# 11_-POWER_BACKUP.net
KiCad netlist of a schematic drawn in Altium Designer
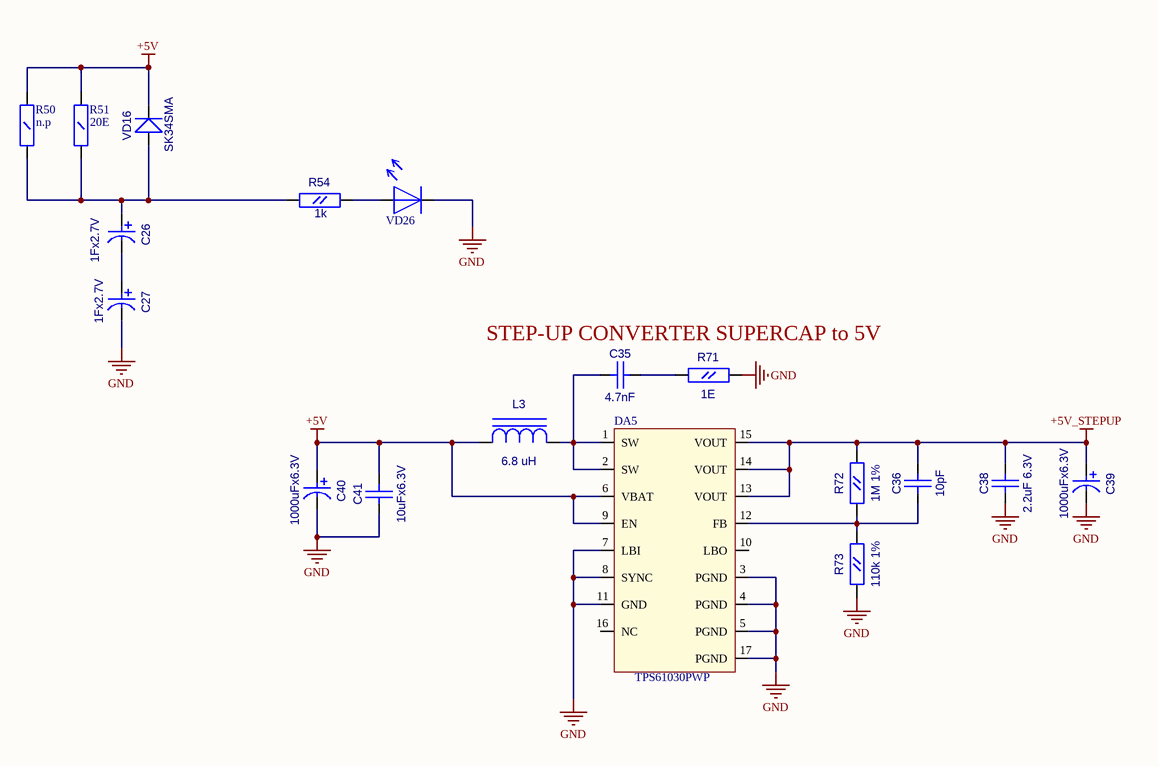
[diagram p0: [11]-POWER_BACKUP.SchDoc]

(export (version "E")
  (design (tool "Eeschema 10.0.6"))
  (components
    (comp (ref "C26")
      (value "1Fx2.7V")
      (footprint "CC8X11.5_L")
      (description "Radial capacitor")
      (libsource (lib "fizik_lib") (part "CAP_8mm"))
    )
    (comp (ref "C27")
      (value "1Fx2.7V")
      (footprint "CC8X11.5_L")
      (description "Radial capacitor")
      (libsource (lib "fizik_lib") (part "CAP_8mm"))
    )
    (comp (ref "C35")
      (value "4.7nF")
      (footprint "CC0603")
      (description "CC0603")
      (libsource (lib "gprs_modem_2") (part "CC0603"))
    )
    (comp (ref "C36")
      (value "10pF")
      (footprint "CC0603")
      (description "CC0603")
      (libsource (lib "gprs_modem_2") (part "CC0603"))
    )
    (comp (ref "C38")
      (value "2.2uF 6.3V")
      (footprint "CC0805")
      (description "CC0805")
      (libsource (lib "gprs_modem_2") (part "CC0805"))
    )
    (comp (ref "C39")
      (value "1000uFx6.3V")
      (footprint "CC8X3.5")
      (description "CAP0.35")
      (libsource (lib "gprs_modem_2") (part "CAP0.35"))
    )
    (comp (ref "C40")
      (value "1000uFx6.3V")
      (footprint "CC8X3.5")
      (description "CAP0.35")
      (libsource (lib "gprs_modem_2") (part "CAP0.35"))
    )
    (comp (ref "C41")
      (value "10uFx6.3V")
      (footprint "CC0805")
      (description "CC0805")
      (libsource (lib "gprs_modem_2") (part "CC0805"))
    )
    (comp (ref "DA5")
      (value "TPS61030PWP")
      (footprint "R-PDSO-G16")
      (description "Boost converter")
      (libsource (lib "gprs_modem") (part "TPS61030PWP"))
    )
    (comp (ref "L3")
      (value "6.8 uH")
      (footprint "SDR0805")
      (description "SDR0805")
      (libsource (lib "gprs_modem_2") (part "SDR0805"))
    )
    (comp (ref "R50")
      (value "n.p")
      (footprint "R2512")
      (description "Resistor 2512 1W")
      (libsource (lib "fizik_lib") (part "RC2512"))
    )
    (comp (ref "R51")
      (value "20E")
      (footprint "R2512")
      (description "Resistor 2512 1W")
      (libsource (lib "fizik_lib") (part "RC2512"))
    )
    (comp (ref "R54")
      (value "1k")
      (footprint "RC0603")
      (description "RC0603")
      (libsource (lib "fizik_lib") (part "RC0603"))
    )
    (comp (ref "R71")
      (value "1E")
      (footprint "RC0603")
      (description "RC0603")
      (libsource (lib "gprs_modem_2") (part "RC0603"))
    )
    (comp (ref "R72")
      (value "1M 1%")
      (footprint "RC0603")
      (description "RC0603")
      (libsource (lib "gprs_modem_2") (part "RC0603"))
    )
    (comp (ref "R73")
      (value "110k 1%")
      (footprint "RC0603")
      (description "RC0603")
      (libsource (lib "gprs_modem_2") (part "RC0603"))
    )
    (comp (ref "VD16")
      (value "SK34SMA")
      (footprint "SMA")
      (description "Schottky Rectifier")
      (libsource (lib "gprs_modem") (part "SK34SMA"))
    )
    (comp (ref "VD26")
      (value "LED_0805")
      (footprint "LED0805")
      (libsource (lib "fizik_lib") (part "LED_0805"))
    )
  )
  (nets
    (net (code "1") (name "+5V") (class "Default")
      (node (ref "C40") (pin "1") (pintype "passive"))
      (node (ref "C41") (pin "2") (pinfunction "B_2") (pintype "passive"))
      (node (ref "DA5") (pin "6") (pinfunction "VBAT_6") (pintype "passive"))
      (node (ref "DA5") (pin "9") (pinfunction "EN_9") (pintype "passive"))
      (node (ref "L3") (pin "1") (pinfunction "C_1") (pintype "passive"))
      (node (ref "R50") (pin "2") (pinfunction "B_2") (pintype "passive"))
      (node (ref "R51") (pin "2") (pinfunction "B_2") (pintype "passive"))
      (node (ref "VD16") (pin "2") (pinfunction "K_2") (pintype "passive"))
    )
    (net (code "2") (name "+5V_STEPUP") (class "Default")
      (node (ref "C36") (pin "2") (pinfunction "B_2") (pintype "passive"))
      (node (ref "C38") (pin "2") (pinfunction "B_2") (pintype "passive"))
      (node (ref "C39") (pin "1") (pintype "passive"))
      (node (ref "DA5") (pin "13") (pinfunction "VOUT_13") (pintype "passive"))
      (node (ref "DA5") (pin "14") (pinfunction "VOUT_14") (pintype "passive"))
      (node (ref "DA5") (pin "15") (pinfunction "VOUT_15") (pintype "passive"))
      (node (ref "R72") (pin "2") (pinfunction "B_2") (pintype "passive"))
    )
    (net (code "3") (name "GND") (class "Default")
      (node (ref "C27") (pin "2") (pintype "passive"))
      (node (ref "C38") (pin "1") (pinfunction "A_1") (pintype "passive"))
      (node (ref "C39") (pin "2") (pintype "passive"))
      (node (ref "C40") (pin "2") (pintype "passive"))
      (node (ref "C41") (pin "1") (pinfunction "A_1") (pintype "passive"))
      (node (ref "DA5") (pin "11") (pinfunction "GND_11") (pintype "passive"))
      (node (ref "DA5") (pin "17") (pinfunction "PGND_17") (pintype "passive"))
      (node (ref "DA5") (pin "3") (pinfunction "PGND_3") (pintype "passive"))
      (node (ref "DA5") (pin "4") (pinfunction "PGND_4") (pintype "passive"))
      (node (ref "DA5") (pin "5") (pinfunction "PGND_5") (pintype "passive"))
      (node (ref "DA5") (pin "7") (pinfunction "LBI_7") (pintype "passive"))
      (node (ref "DA5") (pin "8") (pinfunction "SYNC_8") (pintype "passive"))
      (node (ref "R71") (pin "2") (pinfunction "B_2") (pintype "passive"))
      (node (ref "R73") (pin "1") (pinfunction "A_1") (pintype "passive"))
      (node (ref "VD26") (pin "2") (pintype "passive"))
    )
    (net (code "4") (name "Net-(C26-Pad2)") (class "Default")
      (node (ref "C26") (pin "2") (pintype "passive"))
      (node (ref "C27") (pin "1") (pintype "passive"))
    )
    (net (code "5") (name "Net-(C35-A)") (class "Default")
      (node (ref "C35") (pin "1") (pinfunction "A_1") (pintype "passive"))
      (node (ref "DA5") (pin "1") (pinfunction "SW_1") (pintype "passive"))
      (node (ref "DA5") (pin "2") (pinfunction "SW_2") (pintype "passive"))
      (node (ref "L3") (pin "2") (pinfunction "A_2") (pintype "passive"))
    )
    (net (code "6") (name "Net-(C35-B)") (class "Default")
      (node (ref "C35") (pin "2") (pinfunction "B_2") (pintype "passive"))
      (node (ref "R71") (pin "1") (pinfunction "A_1") (pintype "passive"))
    )
    (net (code "7") (name "Net-(C36-A)") (class "Default")
      (node (ref "C36") (pin "1") (pinfunction "A_1") (pintype "passive"))
      (node (ref "DA5") (pin "12") (pinfunction "FB_12") (pintype "passive"))
      (node (ref "R72") (pin "1") (pinfunction "A_1") (pintype "passive"))
      (node (ref "R73") (pin "2") (pinfunction "B_2") (pintype "passive"))
    )
    (net (code "8") (name "Net-(R50-A)") (class "Default")
      (node (ref "C26") (pin "1") (pintype "passive"))
      (node (ref "R50") (pin "1") (pinfunction "A_1") (pintype "passive"))
      (node (ref "R51") (pin "1") (pinfunction "A_1") (pintype "passive"))
      (node (ref "R54") (pin "1") (pinfunction "A_1") (pintype "passive"))
      (node (ref "VD16") (pin "1") (pinfunction "A_1") (pintype "passive"))
    )
    (net (code "9") (name "Net-(R54-B)") (class "Default")
      (node (ref "R54") (pin "2") (pinfunction "B_2") (pintype "passive"))
      (node (ref "VD26") (pin "1") (pintype "passive"))
    )
    (net (code "10") (name "unconnected-(DA5-LBO-Pad10)") (class "Default")
      (node (ref "DA5") (pin "10") (pinfunction "LBO_10") (pintype "passive"))
    )
    (net (code "11") (name "unconnected-(DA5-NC-Pad16)") (class "Default")
      (node (ref "DA5") (pin "16") (pinfunction "NC_16") (pintype "passive"))
    )
  )
)
